# touch-2ch.net
KiCad netlist of a schematic drawn in Altium Designer
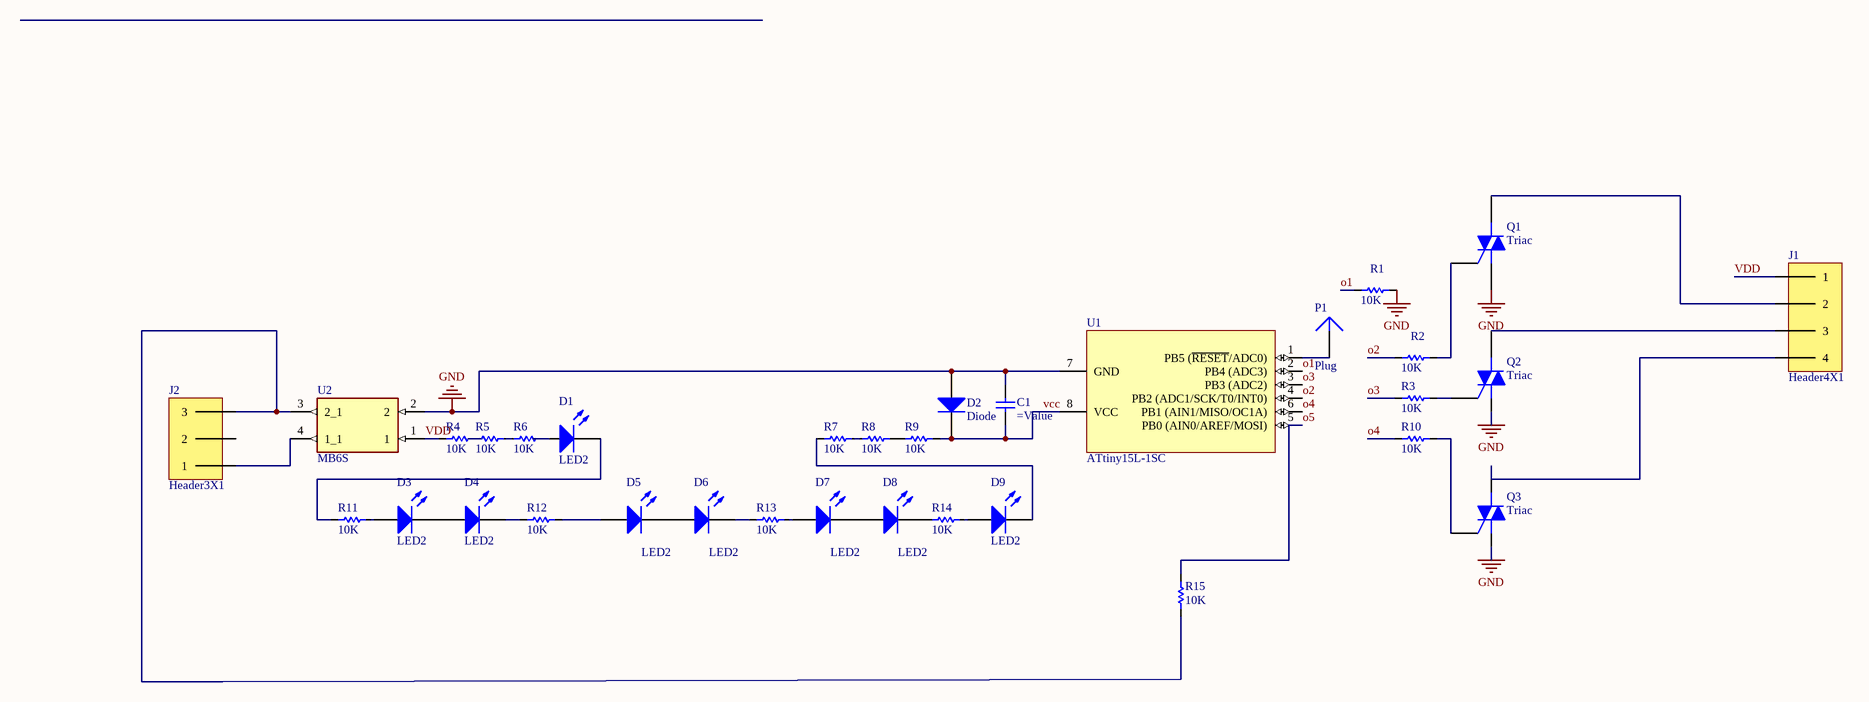
[diagram p0: touch-2ch.SchDoc]

(export (version "E")
  (design (tool "Eeschema 10.0.6"))
  (components
    (comp (ref "C1")
      (value "~")
      (footprint "CAP 1206")
      (description "Capacitor")
      (libsource (lib "AltiumLib1") (part "Capacitor"))
    )
    (comp (ref "D1")
      (value "LED2")
      (footprint "3.2X1.6X1.1")
      (description "Typical RED, GREEN, YELLOW, AMBER GaAs LED")
      (fields (field (name "PUBLISHER") "Altium Limited"))
      (libsource (lib "Miscellaneous Devices") (part "LED2"))
    )
    (comp (ref "D2")
      (value "Diode")
      (footprint "C1206")
      (description "Default Diode")
      (fields (field (name "PUBLISHER") "Altium Limited"))
      (libsource (lib "Miscellaneous Devices") (part "Diode"))
    )
    (comp (ref "D3")
      (value "LED2")
      (footprint "3.2X1.6X1.1")
      (description "Typical RED, GREEN, YELLOW, AMBER GaAs LED")
      (fields (field (name "PUBLISHER") "Altium Limited"))
      (libsource (lib "Miscellaneous Devices") (part "LED2"))
    )
    (comp (ref "D4")
      (value "LED2")
      (footprint "3.2X1.6X1.1")
      (description "Typical RED, GREEN, YELLOW, AMBER GaAs LED")
      (fields (field (name "PUBLISHER") "Altium Limited"))
      (libsource (lib "Miscellaneous Devices") (part "LED2"))
    )
    (comp (ref "D5")
      (value "LED2")
      (footprint "3.2X1.6X1.1")
      (description "Typical RED, GREEN, YELLOW, AMBER GaAs LED")
      (fields (field (name "PUBLISHER") "Altium Limited"))
      (libsource (lib "Miscellaneous Devices") (part "LED2"))
    )
    (comp (ref "D6")
      (value "LED2")
      (footprint "3.2X1.6X1.1")
      (description "Typical RED, GREEN, YELLOW, AMBER GaAs LED")
      (fields (field (name "PUBLISHER") "Altium Limited"))
      (libsource (lib "Miscellaneous Devices") (part "LED2"))
    )
    (comp (ref "D7")
      (value "LED2")
      (footprint "3.2X1.6X1.1")
      (description "Typical RED, GREEN, YELLOW, AMBER GaAs LED")
      (fields (field (name "PUBLISHER") "Altium Limited"))
      (libsource (lib "Miscellaneous Devices") (part "LED2"))
    )
    (comp (ref "D8")
      (value "LED2")
      (footprint "3.2X1.6X1.1")
      (description "Typical RED, GREEN, YELLOW, AMBER GaAs LED")
      (fields (field (name "PUBLISHER") "Altium Limited"))
      (libsource (lib "Miscellaneous Devices") (part "LED2"))
    )
    (comp (ref "D9")
      (value "LED2")
      (footprint "3.2X1.6X1.1")
      (description "Typical RED, GREEN, YELLOW, AMBER GaAs LED")
      (fields (field (name "PUBLISHER") "Altium Limited"))
      (libsource (lib "Miscellaneous Devices") (part "LED2"))
    )
    (comp (ref "J1")
      (value "Header4X1")
      (footprint "HEADER 4X1")
      (libsource (lib "AltiumLib1") (part "Header4X1"))
    )
    (comp (ref "J2")
      (value "Header3X1")
      (footprint "HEADER 3X1")
      (libsource (lib "AltiumLib1") (part "Header3X1"))
    )
    (comp (ref "P1")
      (value "Plug")
      (footprint "PIN1")
      (fields (field (name "PUBLISHER") "Altium Limited"))
      (libsource (lib "Miscellaneous Connectors") (part "Plug"))
    )
    (comp (ref "Q1")
      (value "Triac")
      (footprint "SOT89N")
      (description "Silicon Bidirectional Triode Thyristor")
      (fields (field (name "PUBLISHER") "Altium Limited"))
      (libsource (lib "Miscellaneous Devices") (part "Triac"))
    )
    (comp (ref "Q2")
      (value "Triac")
      (footprint "SOT89N")
      (description "Silicon Bidirectional Triode Thyristor")
      (fields (field (name "PUBLISHER") "Altium Limited"))
      (libsource (lib "Miscellaneous Devices") (part "Triac"))
    )
    (comp (ref "Q3")
      (value "Triac")
      (footprint "SOT89N")
      (description "Silicon Bidirectional Triode Thyristor")
      (fields (field (name "PUBLISHER") "Altium Limited"))
      (libsource (lib "Miscellaneous Devices") (part "Triac"))
    )
    (comp (ref "R1")
      (value "10K")
      (footprint "RES 1206 (3216X08L)")
      (description "Resistor")
      (fields (field (name "TOLERANCE") "5%") (field (name "POWER") "1/4 W"))
      (libsource (lib "AltiumLib1") (part "Resistor"))
    )
    (comp (ref "R2")
      (value "10K")
      (footprint "RES 1206 (3216X08L)")
      (description "Resistor")
      (fields (field (name "TOLERANCE") "5%") (field (name "POWER") "1/4 W"))
      (libsource (lib "AltiumLib1") (part "Resistor"))
    )
    (comp (ref "R3")
      (value "10K")
      (footprint "RES 1206 (3216X08L)")
      (description "Resistor")
      (fields (field (name "TOLERANCE") "5%") (field (name "POWER") "1/4 W"))
      (libsource (lib "AltiumLib1") (part "Resistor"))
    )
    (comp (ref "R4")
      (value "10K")
      (footprint "RES 2010 (5026X08L)")
      (description "Resistor")
      (fields (field (name "TOLERANCE") "5%") (field (name "POWER") "1/4 W"))
      (libsource (lib "AltiumLib1") (part "Resistor"))
    )
    (comp (ref "R5")
      (value "10K")
      (footprint "RES 2010 (5026X08L)")
      (description "Resistor")
      (fields (field (name "TOLERANCE") "5%") (field (name "POWER") "1/4 W"))
      (libsource (lib "AltiumLib1") (part "Resistor"))
    )
    (comp (ref "R6")
      (value "10K")
      (footprint "RES 2010 (5026X08L)")
      (description "Resistor")
      (fields (field (name "TOLERANCE") "5%") (field (name "POWER") "1/4 W"))
      (libsource (lib "AltiumLib1") (part "Resistor"))
    )
    (comp (ref "R7")
      (value "10K")
      (footprint "RES 2010 (5026X08L)")
      (description "Resistor")
      (fields (field (name "TOLERANCE") "5%") (field (name "POWER") "1/4 W"))
      (libsource (lib "AltiumLib1") (part "Resistor"))
    )
    (comp (ref "R8")
      (value "10K")
      (footprint "RES 2010 (5026X08L)")
      (description "Resistor")
      (fields (field (name "TOLERANCE") "5%") (field (name "POWER") "1/4 W"))
      (libsource (lib "AltiumLib1") (part "Resistor"))
    )
    (comp (ref "R9")
      (value "10K")
      (footprint "RES 2010 (5026X08L)")
      (description "Resistor")
      (fields (field (name "TOLERANCE") "5%") (field (name "POWER") "1/4 W"))
      (libsource (lib "AltiumLib1") (part "Resistor"))
    )
    (comp (ref "R10")
      (value "10K")
      (footprint "RES 1206 (3216X08L)")
      (description "Resistor")
      (fields (field (name "TOLERANCE") "5%") (field (name "POWER") "1/4 W"))
      (libsource (lib "AltiumLib1") (part "Resistor"))
    )
    (comp (ref "R11")
      (value "10K")
      (footprint "RES 2010 (5026X08L)")
      (description "Resistor")
      (fields (field (name "TOLERANCE") "5%") (field (name "POWER") "1/4 W"))
      (libsource (lib "AltiumLib1") (part "Resistor"))
    )
    (comp (ref "R12")
      (value "10K")
      (footprint "RES 2010 (5026X08L)")
      (description "Resistor")
      (fields (field (name "TOLERANCE") "5%") (field (name "POWER") "1/4 W"))
      (libsource (lib "AltiumLib1") (part "Resistor"))
    )
    (comp (ref "R13")
      (value "10K")
      (footprint "RES 2010 (5026X08L)")
      (description "Resistor")
      (fields (field (name "TOLERANCE") "5%") (field (name "POWER") "1/4 W"))
      (libsource (lib "AltiumLib1") (part "Resistor"))
    )
    (comp (ref "R14")
      (value "10K")
      (footprint "RES 2010 (5026X08L)")
      (description "Resistor")
      (fields (field (name "TOLERANCE") "5%") (field (name "POWER") "1/4 W"))
      (libsource (lib "AltiumLib1") (part "Resistor"))
    )
    (comp (ref "R15")
      (value "10K")
      (footprint "RES 1206 (3216X08L)")
      (description "Resistor")
      (fields (field (name "TOLERANCE") "5%") (field (name "POWER") "1/4 W"))
      (libsource (lib "AltiumLib1") (part "Resistor"))
    )
    (comp (ref "U1")
      (value "ATtiny15L-1SC")
      (footprint "8S2_N")
      (description "8-Bit AVR Microcontroller with 1K Byte of Flash Memory")
      (fields (field (name "PUBLISHER") "Altium Limited"))
      (libsource (lib "Atmel Microcontroller 8-Bit AVR") (part "ATtiny15L-1SC"))
    )
    (comp (ref "U2")
      (value "MB6S")
      (footprint "SOIC245P670X270-4N")
      (description "Bridge Rectifier Single Phase Standard 600V Surface Mount 4-SOIC")
      (fields (field (name "MF") "ON Semiconductor") (field (name "DIGI-KEY_PART_NUMBER") "MB6SCT-ND"))
      (libsource (lib "MB6S") (part "MB6S"))
    )
  )
  (nets
    (net (code "1") (name "/VDD") (class "Default")
      (node (ref "J1") (pin "1") (pinfunction "1_1") (pintype "passive"))
      (node (ref "R4") (pin "1") (pinfunction "1_1") (pintype "passive"))
      (node (ref "U2") (pin "1") (pinfunction "1_1") (pintype "input"))
    )
    (net (code "2") (name "/o1") (class "Default")
      (node (ref "R1") (pin "1") (pinfunction "1_1") (pintype "passive"))
      (node (ref "U1") (pin "2") (pinfunction "PB4_(ADC3)_2") (pintype "bidirectional"))
    )
    (net (code "3") (name "/o2") (class "Default")
      (node (ref "R2") (pin "1") (pinfunction "1_1") (pintype "passive"))
      (node (ref "U1") (pin "4") (pinfunction "PB2_(ADC1/SCK/T0/INT0)_4") (pintype "bidirectional"))
    )
    (net (code "4") (name "/o3") (class "Default")
      (node (ref "R3") (pin "1") (pinfunction "1_1") (pintype "passive"))
      (node (ref "U1") (pin "3") (pinfunction "PB3_(ADC2)_3") (pintype "bidirectional"))
    )
    (net (code "5") (name "/o4") (class "Default")
      (node (ref "R10") (pin "1") (pinfunction "1_1") (pintype "passive"))
      (node (ref "U1") (pin "6") (pinfunction "PB1_(AIN1/MISO/OC1A)_6") (pintype "bidirectional"))
    )
    (net (code "6") (name "/o5") (class "Default")
      (node (ref "R15") (pin "2") (pinfunction "2_2") (pintype "passive"))
      (node (ref "U1") (pin "5") (pinfunction "PB0_(AIN0/AREF/MOSI)_5") (pintype "bidirectional"))
    )
    (net (code "7") (name "/vcc") (class "Default")
      (node (ref "C1") (pin "1") (pinfunction "+_1") (pintype "passive"))
      (node (ref "D2") (pin "2") (pinfunction "K_2") (pintype "passive"))
      (node (ref "R9") (pin "2") (pinfunction "2_2") (pintype "passive"))
      (node (ref "U1") (pin "8") (pinfunction "VCC_8") (pintype "power_in"))
    )
    (net (code "8") (name "GND") (class "Default")
      (node (ref "C1") (pin "2") (pinfunction "-_2") (pintype "passive"))
      (node (ref "D2") (pin "1") (pinfunction "A_1") (pintype "passive"))
      (node (ref "Q1") (pin "1") (pinfunction "M1_1") (pintype "passive"))
      (node (ref "Q2") (pin "1") (pinfunction "M1_1") (pintype "passive"))
      (node (ref "Q3") (pin "1") (pinfunction "M1_1") (pintype "passive"))
      (node (ref "R1") (pin "2") (pinfunction "2_2") (pintype "passive"))
      (node (ref "U1") (pin "7") (pinfunction "GND_7") (pintype "power_in"))
      (node (ref "U2") (pin "2") (pinfunction "2_2") (pintype "input"))
    )
    (net (code "9") (name "Net-(D1-A)") (class "Default")
      (node (ref "D1") (pin "1") (pinfunction "A_1") (pintype "passive"))
      (node (ref "R6") (pin "2") (pinfunction "2_2") (pintype "passive"))
    )
    (net (code "10") (name "Net-(D1-K)") (class "Default")
      (node (ref "D1") (pin "2") (pinfunction "K_2") (pintype "passive"))
      (node (ref "R11") (pin "1") (pinfunction "1_1") (pintype "passive"))
    )
    (net (code "11") (name "Net-(D3-A)") (class "Default")
      (node (ref "D3") (pin "1") (pinfunction "A_1") (pintype "passive"))
      (node (ref "R11") (pin "2") (pinfunction "2_2") (pintype "passive"))
    )
    (net (code "12") (name "Net-(D3-K)") (class "Default")
      (node (ref "D3") (pin "2") (pinfunction "K_2") (pintype "passive"))
      (node (ref "D4") (pin "1") (pinfunction "A_1") (pintype "passive"))
    )
    (net (code "13") (name "Net-(D4-K)") (class "Default")
      (node (ref "D4") (pin "2") (pinfunction "K_2") (pintype "passive"))
      (node (ref "R12") (pin "1") (pinfunction "1_1") (pintype "passive"))
    )
    (net (code "14") (name "Net-(D5-A)") (class "Default")
      (node (ref "D5") (pin "1") (pinfunction "A_1") (pintype "passive"))
      (node (ref "R12") (pin "2") (pinfunction "2_2") (pintype "passive"))
    )
    (net (code "15") (name "Net-(D5-K)") (class "Default")
      (node (ref "D5") (pin "2") (pinfunction "K_2") (pintype "passive"))
      (node (ref "D6") (pin "1") (pinfunction "A_1") (pintype "passive"))
    )
    (net (code "16") (name "Net-(D6-K)") (class "Default")
      (node (ref "D6") (pin "2") (pinfunction "K_2") (pintype "passive"))
      (node (ref "R13") (pin "1") (pinfunction "1_1") (pintype "passive"))
    )
    (net (code "17") (name "Net-(D7-A)") (class "Default")
      (node (ref "D7") (pin "1") (pinfunction "A_1") (pintype "passive"))
      (node (ref "R13") (pin "2") (pinfunction "2_2") (pintype "passive"))
    )
    (net (code "18") (name "Net-(D7-K)") (class "Default")
      (node (ref "D7") (pin "2") (pinfunction "K_2") (pintype "passive"))
      (node (ref "D8") (pin "1") (pinfunction "A_1") (pintype "passive"))
    )
    (net (code "19") (name "Net-(D8-K)") (class "Default")
      (node (ref "D8") (pin "2") (pinfunction "K_2") (pintype "passive"))
      (node (ref "R14") (pin "1") (pinfunction "1_1") (pintype "passive"))
    )
    (net (code "20") (name "Net-(D9-A)") (class "Default")
      (node (ref "D9") (pin "1") (pinfunction "A_1") (pintype "passive"))
      (node (ref "R14") (pin "2") (pinfunction "2_2") (pintype "passive"))
    )
    (net (code "21") (name "Net-(D9-K)") (class "Default")
      (node (ref "D9") (pin "2") (pinfunction "K_2") (pintype "passive"))
      (node (ref "R7") (pin "1") (pinfunction "1_1") (pintype "passive"))
    )
    (net (code "22") (name "Net-(Q1-G)") (class "Default")
      (node (ref "Q1") (pin "3") (pinfunction "G_3") (pintype "passive"))
      (node (ref "R2") (pin "2") (pinfunction "2_2") (pintype "passive"))
    )
    (net (code "23") (name "Net-(Q1-M2)") (class "Default")
      (node (ref "J1") (pin "2") (pinfunction "2_2") (pintype "passive"))
      (node (ref "Q1") (pin "2") (pinfunction "M2_2") (pintype "passive"))
    )
    (net (code "24") (name "Net-(Q2-G)") (class "Default")
      (node (ref "Q2") (pin "3") (pinfunction "G_3") (pintype "passive"))
      (node (ref "R3") (pin "2") (pinfunction "2_2") (pintype "passive"))
    )
    (net (code "25") (name "Net-(Q2-M2)") (class "Default")
      (node (ref "J1") (pin "3") (pinfunction "3_3") (pintype "passive"))
      (node (ref "Q2") (pin "2") (pinfunction "M2_2") (pintype "passive"))
    )
    (net (code "26") (name "Net-(Q3-G)") (class "Default")
      (node (ref "Q3") (pin "3") (pinfunction "G_3") (pintype "passive"))
      (node (ref "R10") (pin "2") (pinfunction "2_2") (pintype "passive"))
    )
    (net (code "27") (name "Net-(Q3-M2)") (class "Default")
      (node (ref "J1") (pin "4") (pinfunction "4_4") (pintype "passive"))
      (node (ref "Q3") (pin "2") (pinfunction "M2_2") (pintype "passive"))
    )
    (net (code "28") (name "Net-(R4-Pad2)") (class "Default")
      (node (ref "R4") (pin "2") (pinfunction "2_2") (pintype "passive"))
      (node (ref "R5") (pin "1") (pinfunction "1_1") (pintype "passive"))
    )
    (net (code "29") (name "Net-(R5-Pad2)") (class "Default")
      (node (ref "R5") (pin "2") (pinfunction "2_2") (pintype "passive"))
      (node (ref "R6") (pin "1") (pinfunction "1_1") (pintype "passive"))
    )
    (net (code "30") (name "Net-(R7-Pad2)") (class "Default")
      (node (ref "R7") (pin "2") (pinfunction "2_2") (pintype "passive"))
      (node (ref "R8") (pin "1") (pinfunction "1_1") (pintype "passive"))
    )
    (net (code "31") (name "Net-(R8-Pad2)") (class "Default")
      (node (ref "R8") (pin "2") (pinfunction "2_2") (pintype "passive"))
      (node (ref "R9") (pin "1") (pinfunction "1_1") (pintype "passive"))
    )
    (net (code "32") (name "Net-(U1-PB5_(~{RESET}{slash}ADC0))") (class "Default")
      (node (ref "P1") (pin "1") (pinfunction "1_1") (pintype "passive"))
      (node (ref "U1") (pin "1") (pinfunction "PB5_(~{RESET}/ADC0)_1") (pintype "bidirectional"))
    )
    (net (code "33") (name "Net-(U2-1_1)") (class "Default")
      (node (ref "J2") (pin "1") (pinfunction "1_1") (pintype "passive"))
      (node (ref "U2") (pin "4") (pinfunction "1_1_4") (pintype "output"))
    )
    (net (code "34") (name "Net-(U2-2_1)") (class "Default")
      (node (ref "J2") (pin "3") (pinfunction "3_3") (pintype "passive"))
      (node (ref "R15") (pin "1") (pinfunction "1_1") (pintype "passive"))
      (node (ref "U2") (pin "3") (pinfunction "2_1_3") (pintype "output"))
    )
    (net (code "35") (name "unconnected-(J2-Pad2)") (class "Default")
      (node (ref "J2") (pin "2") (pinfunction "2_2") (pintype "passive"))
    )
  )
)
